# example.net
KiCad netlist of a schematic drawn in EAGLE
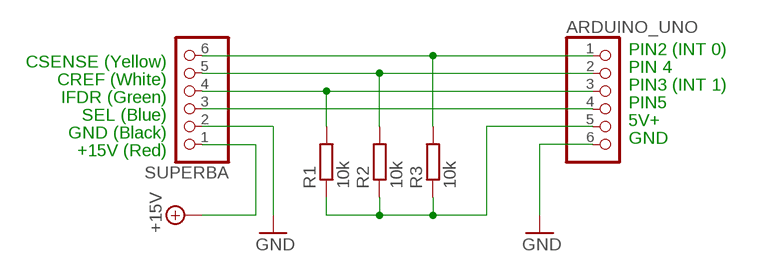
[diagram p0: schematic, sheet 1]

(export (version "E")
  (design (tool "Eeschema 10.0.6"))
  (components
    (comp (ref "ARDUINO_UNO")
      (value "PINHD-1X6")
      (footprint "eagle-import:1X06")
      (libsource (lib "eagle-import") (part "PINHD-1X6"))
    )
    (comp (ref "R1")
      (value "10k")
      (footprint "eagle-import:0309_12")
      (libsource (lib "eagle-import") (part "R-EU_0309/12"))
    )
    (comp (ref "R2")
      (value "10k")
      (footprint "eagle-import:0309_12")
      (libsource (lib "eagle-import") (part "R-EU_0309/12"))
    )
    (comp (ref "R3")
      (value "10k")
      (footprint "eagle-import:0309_12")
      (libsource (lib "eagle-import") (part "R-EU_0309/12"))
    )
    (comp (ref "SUPERBA")
      (value "PINHD-1X6")
      (footprint "eagle-import:1X06")
      (libsource (lib "eagle-import") (part "PINHD-1X6"))
    )
  )
  (nets
    (net (code "1") (name "+15V") (class "Default")
      (node (ref "SUPERBA") (pin "1") (pinfunction "1_1") (pintype "passive"))
    )
    (net (code "2") (name "GND") (class "Default")
      (node (ref "ARDUINO_UNO") (pin "6") (pinfunction "6_6") (pintype "passive"))
      (node (ref "SUPERBA") (pin "2") (pinfunction "2_2") (pintype "passive"))
    )
    (net (code "3") (name "Net-(ARDUINO_UNO-Pad1)") (class "Default")
      (node (ref "ARDUINO_UNO") (pin "1") (pinfunction "1_1") (pintype "passive"))
      (node (ref "R3") (pin "2") (pinfunction "2_2") (pintype "passive"))
      (node (ref "SUPERBA") (pin "6") (pinfunction "6_6") (pintype "passive"))
    )
    (net (code "4") (name "Net-(ARDUINO_UNO-Pad2)") (class "Default")
      (node (ref "ARDUINO_UNO") (pin "2") (pinfunction "2_2") (pintype "passive"))
      (node (ref "R2") (pin "2") (pinfunction "2_2") (pintype "passive"))
      (node (ref "SUPERBA") (pin "5") (pinfunction "5_5") (pintype "passive"))
    )
    (net (code "5") (name "Net-(ARDUINO_UNO-Pad3)") (class "Default")
      (node (ref "ARDUINO_UNO") (pin "3") (pinfunction "3_3") (pintype "passive"))
      (node (ref "R1") (pin "2") (pinfunction "2_2") (pintype "passive"))
      (node (ref "SUPERBA") (pin "4") (pinfunction "4_4") (pintype "passive"))
    )
    (net (code "6") (name "Net-(ARDUINO_UNO-Pad4)") (class "Default")
      (node (ref "ARDUINO_UNO") (pin "4") (pinfunction "4_4") (pintype "passive"))
      (node (ref "SUPERBA") (pin "3") (pinfunction "3_3") (pintype "passive"))
    )
    (net (code "7") (name "Net-(ARDUINO_UNO-Pad5)") (class "Default")
      (node (ref "ARDUINO_UNO") (pin "5") (pinfunction "5_5") (pintype "passive"))
      (node (ref "R1") (pin "1") (pinfunction "1_1") (pintype "passive"))
      (node (ref "R2") (pin "1") (pinfunction "1_1") (pintype "passive"))
      (node (ref "R3") (pin "1") (pinfunction "1_1") (pintype "passive"))
    )
  )
)
